# Ethernet.net
KiCad netlist of a schematic drawn in Altium Designer
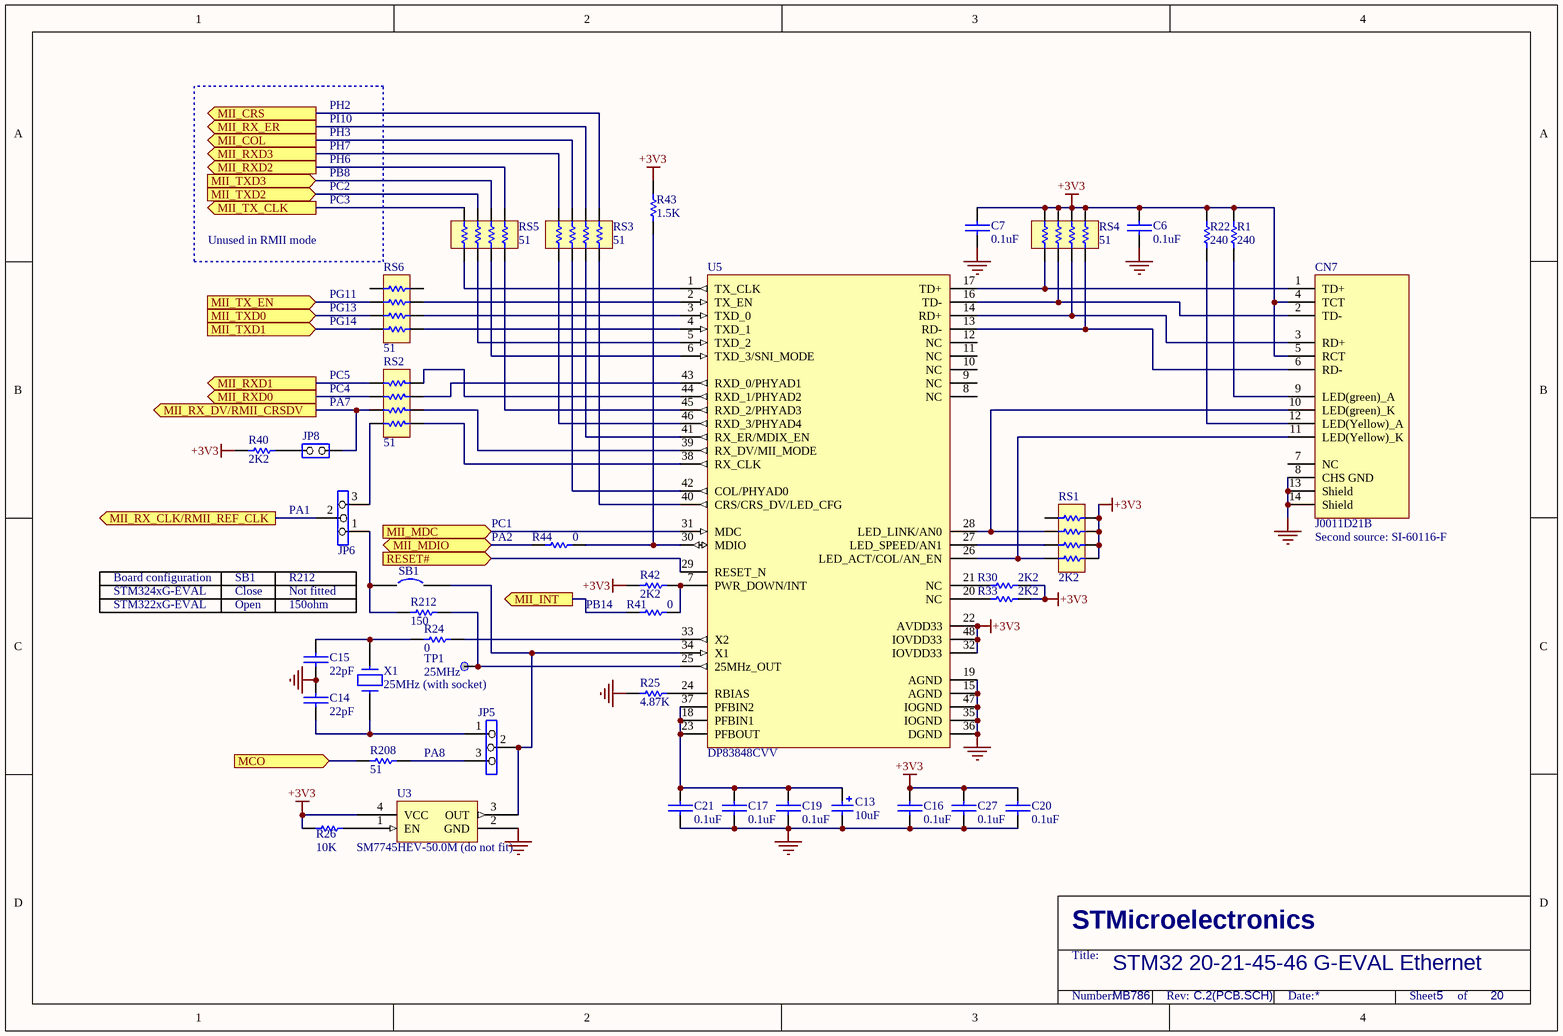
[diagram p0: Ethernet.SchDoc]

(export (version "E")
  (design (tool "Eeschema 10.0.6"))
  (components
    (comp (ref "C6")
      (value "0.1uF")
      (footprint "0402C")
      (description "Capacitor")
      (libsource (lib "*") (part "CAP"))
    )
    (comp (ref "C7")
      (value "0.1uF")
      (footprint "0402C")
      (description "Capacitor")
      (libsource (lib "*") (part "CAP"))
    )
    (comp (ref "C13")
      (value "10uF")
      (footprint "TAN-A")
      (description "Polarized Capacitor (Radial)")
      (fields (field (name "PUBLISHER") "Altium Limited"))
      (libsource (lib "Miscellaneous Devices") (part "Cap Pol1"))
    )
    (comp (ref "C14")
      (value "22pF")
      (footprint "0603C")
      (description "Capacitor")
      (libsource (lib "*") (part "CAP"))
    )
    (comp (ref "C15")
      (value "22pF")
      (footprint "0603C")
      (description "Capacitor")
      (libsource (lib "*") (part "CAP"))
    )
    (comp (ref "C16")
      (value "0.1uF")
      (footprint "0402C")
      (description "Capacitor")
      (libsource (lib "*") (part "CAP"))
    )
    (comp (ref "C17")
      (value "0.1uF")
      (footprint "0402C")
      (description "Capacitor")
      (libsource (lib "*") (part "CAP"))
    )
    (comp (ref "C19")
      (value "0.1uF")
      (footprint "0402C")
      (description "Capacitor")
      (libsource (lib "*") (part "CAP"))
    )
    (comp (ref "C20")
      (value "0.1uF")
      (footprint "0402C")
      (description "Capacitor")
      (libsource (lib "*") (part "CAP"))
    )
    (comp (ref "C21")
      (value "0.1uF")
      (footprint "0402C")
      (description "Capacitor")
      (libsource (lib "*") (part "CAP"))
    )
    (comp (ref "C27")
      (value "0.1uF")
      (footprint "0402C")
      (description "Capacitor")
      (libsource (lib "*") (part "CAP"))
    )
    (comp (ref "CN7")
      (value "J0011D21B")
      (footprint "J0011D21B")
      (libsource (lib "MB784") (part "J0011D21B"))
    )
    (comp (ref "JP5") (value "~") (footprint "SIP3") (libsource (lib "STR910_SCHLIB") (part "Jumper3")))
    (comp (ref "JP6") (value "~") (footprint "SIP3") (libsource (lib "STR910_SCHLIB") (part "Jumper3")))
    (comp (ref "JP8") (value "~") (footprint "SIP2") (libsource (lib "*") (part "JP2")))
    (comp (ref "R1")
      (value "240")
      (footprint "0603R")
      (description "Resistor")
      (fields (field (name "PUBLISHER") "Altium Limited"))
      (libsource (lib "Miscellaneous Devices") (part "Res1"))
    )
    (comp (ref "R22")
      (value "240")
      (footprint "0603R")
      (description "Resistor")
      (fields (field (name "PUBLISHER") "Altium Limited"))
      (libsource (lib "Miscellaneous Devices") (part "Res1"))
    )
    (comp (ref "R24")
      (value "0")
      (footprint "0603R")
      (description "Resistor")
      (fields (field (name "PUBLISHER") "Altium Limited"))
      (libsource (lib "Miscellaneous Devices") (part "Res1"))
    )
    (comp (ref "R25")
      (value "4.87K")
      (footprint "0603R")
      (description "Resistor")
      (fields (field (name "PUBLISHER") "Altium Limited"))
      (libsource (lib "Miscellaneous Devices") (part "Res1"))
    )
    (comp (ref "R26")
      (value "10K")
      (footprint "0402R")
      (description "Resistor")
      (fields (field (name "PUBLISHER") "Altium Limited"))
      (libsource (lib "Miscellaneous Devices") (part "Res1"))
    )
    (comp (ref "R30")
      (value "2K2")
      (footprint "0603R")
      (description "Resistor")
      (fields (field (name "PUBLISHER") "Altium Limited"))
      (libsource (lib "Miscellaneous Devices") (part "Res1"))
    )
    (comp (ref "R33")
      (value "2K2")
      (footprint "0603R")
      (description "Resistor")
      (fields (field (name "PUBLISHER") "Altium Limited"))
      (libsource (lib "Miscellaneous Devices") (part "Res1"))
    )
    (comp (ref "R40")
      (value "2K2")
      (footprint "0603R")
      (description "Resistor")
      (fields (field (name "PUBLISHER") "Altium Limited"))
      (libsource (lib "Miscellaneous Devices") (part "Res1"))
    )
    (comp (ref "R41")
      (value "0")
      (footprint "0603R")
      (description "Resistor")
      (fields (field (name "PUBLISHER") "Altium Limited"))
      (libsource (lib "Miscellaneous Devices") (part "Res1"))
    )
    (comp (ref "R42")
      (value "2K2")
      (footprint "0603R")
      (description "Resistor")
      (fields (field (name "PUBLISHER") "Altium Limited"))
      (libsource (lib "Miscellaneous Devices") (part "Res1"))
    )
    (comp (ref "R43")
      (value "1.5K")
      (footprint "0603R")
      (description "Resistor")
      (fields (field (name "PUBLISHER") "Altium Limited"))
      (libsource (lib "Miscellaneous Devices") (part "Res1"))
    )
    (comp (ref "R44")
      (value "0")
      (footprint "0603R")
      (description "Resistor")
      (fields (field (name "PUBLISHER") "Altium Limited"))
      (libsource (lib "Miscellaneous Devices") (part "Res1"))
    )
    (comp (ref "R208")
      (value "51")
      (footprint "0603R")
      (description "Resistor")
      (fields (field (name "PUBLISHER") "Altium Limited"))
      (libsource (lib "Miscellaneous Devices") (part "Res1"))
    )
    (comp (ref "R212")
      (value "150")
      (footprint "0603R")
      (description "Resistor")
      (fields (field (name "PUBLISHER") "Altium Limited"))
      (libsource (lib "Miscellaneous Devices") (part "Res1"))
    )
    (comp (ref "RS1") (value "2K2") (footprint "RES4B") (libsource (lib "MB784") (part "Resister Array")))
    (comp (ref "RS2") (value "51") (footprint "RES4B") (libsource (lib "*") (part "Resister Array")))
    (comp (ref "RS3") (value "51") (footprint "RES4B") (libsource (lib "") (part "Resister Array_2")))
    (comp (ref "RS4") (value "51") (footprint "RES4B") (libsource (lib "") (part "Resister Array_1")))
    (comp (ref "RS5") (value "51") (footprint "RES4B") (libsource (lib "") (part "Resister Array_2")))
    (comp (ref "RS6") (value "51") (footprint "RES4B") (libsource (lib "MB784") (part "Resister Array")))
    (comp (ref "SB1")
      (value "~")
      (footprint "JP2_SMD")
      (description "Circuit Breaker")
      (fields (field (name "PUBLISHER") "Altium Limited"))
      (libsource (lib "Miscellaneous Devices") (part "Circuit Breaker"))
    )
    (comp (ref "TP1") (value "25MHz") (footprint "TP") (libsource (lib "*") (part "TP")))
    (comp (ref "U3")
      (value "SM7745HEV-50.0M (do not fit)")
      (footprint "XTAL_5X7")
      (libsource (lib "MB784") (part "SM7745HEV-50.0M"))
    )
    (comp (ref "U5") (value "DP83848CVV") (footprint "LQFP48") (libsource (lib "MB784") (part "DP83848CVV")))
    (comp (ref "X1")
      (value "25MHz (with socket)")
      (footprint "XTAL_socket")
      (description "Crystal")
      (libsource (lib "*") (part "CRYSTAL"))
    )
  )
  (nets
    (net (code "1") (name "+3V3") (class "Default")
      (node (ref "C16") (pin "1") (pinfunction "1_1") (pintype "passive"))
      (node (ref "C20") (pin "2") (pinfunction "2_2") (pintype "passive"))
      (node (ref "C27") (pin "2") (pinfunction "2_2") (pintype "passive"))
      (node (ref "C6") (pin "2") (pinfunction "2_2") (pintype "passive"))
      (node (ref "C7") (pin "2") (pinfunction "2_2") (pintype "passive"))
      (node (ref "CN7") (pin "4") (pinfunction "TCT_4") (pintype "passive"))
      (node (ref "CN7") (pin "5") (pinfunction "RCT_5") (pintype "passive"))
      (node (ref "R1") (pin "2") (pinfunction "2_2") (pintype "passive"))
      (node (ref "R22") (pin "2") (pinfunction "2_2") (pintype "passive"))
      (node (ref "R26") (pin "1") (pinfunction "1_1") (pintype "passive"))
      (node (ref "R30") (pin "2") (pinfunction "2_2") (pintype "passive"))
      (node (ref "R33") (pin "2") (pinfunction "2_2") (pintype "passive"))
      (node (ref "R40") (pin "2") (pinfunction "2_2") (pintype "passive"))
      (node (ref "R42") (pin "1") (pinfunction "1_1") (pintype "passive"))
      (node (ref "R43") (pin "2") (pinfunction "2_2") (pintype "passive"))
      (node (ref "RS1") (pin "1") (pinfunction "1_1") (pintype "passive"))
      (node (ref "RS1") (pin "3") (pinfunction "3_3") (pintype "passive"))
      (node (ref "RS1") (pin "5") (pinfunction "5_5") (pintype "passive"))
      (node (ref "RS1") (pin "7") (pinfunction "7_7") (pintype "passive"))
      (node (ref "RS4") (pin "1") (pinfunction "1_1") (pintype "passive"))
      (node (ref "RS4") (pin "3") (pinfunction "3_3") (pintype "passive"))
      (node (ref "RS4") (pin "5") (pinfunction "5_5") (pintype "passive"))
      (node (ref "RS4") (pin "7") (pinfunction "7_7") (pintype "passive"))
      (node (ref "U3") (pin "4") (pinfunction "VCC_4") (pintype "passive"))
      (node (ref "U5") (pin "22") (pinfunction "AVDD33_22") (pintype "passive"))
      (node (ref "U5") (pin "32") (pinfunction "IOVDD33_32") (pintype "passive"))
      (node (ref "U5") (pin "48") (pinfunction "IOVDD33_48") (pintype "passive"))
    )
    (net (code "2") (name "/MCO") (class "Default")
      (node (ref "R208") (pin "2") (pinfunction "2_2") (pintype "passive"))
    )
    (net (code "3") (name "/MII_COL") (class "Default")
      (node (ref "RS3") (pin "4") (pinfunction "4_4") (pintype "passive"))
    )
    (net (code "4") (name "/MII_CRS") (class "Default")
      (node (ref "RS3") (pin "8") (pinfunction "8_8") (pintype "passive"))
    )
    (net (code "5") (name "/MII_INT") (class "Default")
      (node (ref "R41") (pin "1") (pinfunction "1_1") (pintype "passive"))
    )
    (net (code "6") (name "/MII_MDC") (class "Default")
      (node (ref "U5") (pin "31") (pinfunction "MDC_31") (pintype "input"))
    )
    (net (code "7") (name "/MII_MDIO") (class "Default")
      (node (ref "R44") (pin "1") (pinfunction "1_1") (pintype "passive"))
    )
    (net (code "8") (name "/MII_RXD0") (class "Default")
      (node (ref "RS2") (pin "4") (pinfunction "4_4") (pintype "passive"))
    )
    (net (code "9") (name "/MII_RXD1") (class "Default")
      (node (ref "RS2") (pin "2") (pinfunction "2_2") (pintype "passive"))
    )
    (net (code "10") (name "/MII_RXD2") (class "Default")
      (node (ref "RS5") (pin "8") (pinfunction "8_8") (pintype "passive"))
    )
    (net (code "11") (name "/MII_RXD3") (class "Default")
      (node (ref "RS3") (pin "2") (pinfunction "2_2") (pintype "passive"))
    )
    (net (code "12") (name "/MII_RX_CLK{slash}RMII_REF_CLK") (class "Default")
      (node (ref "JP6") (pin "2") (pintype "passive"))
    )
    (net (code "13") (name "/MII_RX_DV{slash}RMII_CRSDV") (class "Default")
      (node (ref "JP8") (pin "1") (pinfunction "COMMON_1") (pintype "passive"))
      (node (ref "RS2") (pin "6") (pinfunction "6_6") (pintype "passive"))
    )
    (net (code "14") (name "/MII_RX_ER") (class "Default")
      (node (ref "RS3") (pin "6") (pinfunction "6_6") (pintype "passive"))
    )
    (net (code "15") (name "/MII_TXD0") (class "Default")
      (node (ref "RS6") (pin "4") (pinfunction "4_4") (pintype "passive"))
    )
    (net (code "16") (name "/MII_TXD1") (class "Default")
      (node (ref "RS6") (pin "2") (pinfunction "2_2") (pintype "passive"))
    )
    (net (code "17") (name "/MII_TXD2") (class "Default")
      (node (ref "RS5") (pin "4") (pinfunction "4_4") (pintype "passive"))
    )
    (net (code "18") (name "/MII_TXD3") (class "Default")
      (node (ref "RS5") (pin "6") (pinfunction "6_6") (pintype "passive"))
    )
    (net (code "19") (name "/MII_TX_CLK") (class "Default")
      (node (ref "RS5") (pin "2") (pinfunction "2_2") (pintype "passive"))
    )
    (net (code "20") (name "/MII_TX_EN") (class "Default")
      (node (ref "RS6") (pin "6") (pinfunction "6_6") (pintype "passive"))
    )
    (net (code "21") (name "/RESET#") (class "Default")
      (node (ref "U5") (pin "29") (pinfunction "RESET_N_29") (pintype "passive"))
    )
    (net (code "22") (name "GND") (class "Default")
      (node (ref "C13") (pin "2") (pinfunction "2_2") (pintype "passive"))
      (node (ref "C14") (pin "2") (pinfunction "2_2") (pintype "passive"))
      (node (ref "C15") (pin "1") (pinfunction "1_1") (pintype "passive"))
      (node (ref "C16") (pin "2") (pinfunction "2_2") (pintype "passive"))
      (node (ref "C17") (pin "1") (pinfunction "1_1") (pintype "passive"))
      (node (ref "C19") (pin "1") (pinfunction "1_1") (pintype "passive"))
      (node (ref "C20") (pin "1") (pinfunction "1_1") (pintype "passive"))
      (node (ref "C21") (pin "2") (pinfunction "2_2") (pintype "passive"))
      (node (ref "C27") (pin "1") (pinfunction "1_1") (pintype "passive"))
      (node (ref "C6") (pin "1") (pinfunction "1_1") (pintype "passive"))
      (node (ref "C7") (pin "1") (pinfunction "1_1") (pintype "passive"))
      (node (ref "CN7") (pin "13") (pinfunction "Shield_13") (pintype "passive"))
      (node (ref "CN7") (pin "14") (pinfunction "Shield_14") (pintype "passive"))
      (node (ref "CN7") (pin "8") (pinfunction "CHS_GND_8") (pintype "passive"))
      (node (ref "R25") (pin "1") (pinfunction "1_1") (pintype "passive"))
      (node (ref "U3") (pin "2") (pinfunction "GND_2") (pintype "passive"))
      (node (ref "U5") (pin "15") (pinfunction "AGND_15") (pintype "passive"))
      (node (ref "U5") (pin "19") (pinfunction "AGND_19") (pintype "passive"))
      (node (ref "U5") (pin "35") (pinfunction "IOGND_35") (pintype "passive"))
      (node (ref "U5") (pin "36") (pinfunction "DGND_36") (pintype "passive"))
      (node (ref "U5") (pin "47") (pinfunction "IOGND_47") (pintype "passive"))
    )
    (net (code "23") (name "Net-(C14-Pad1)") (class "Default")
      (node (ref "C14") (pin "1") (pinfunction "1_1") (pintype "passive"))
      (node (ref "JP5") (pin "1") (pintype "passive"))
      (node (ref "X1") (pin "1") (pinfunction "1_1") (pintype "passive"))
    )
    (net (code "24") (name "Net-(C15-Pad2)") (class "Default")
      (node (ref "C15") (pin "2") (pinfunction "2_2") (pintype "passive"))
      (node (ref "R24") (pin "2") (pinfunction "2_2") (pintype "passive"))
      (node (ref "X1") (pin "2") (pinfunction "2_2") (pintype "passive"))
    )
    (net (code "25") (name "Net-(CN7-LED(Yellow)_A)") (class "Default")
      (node (ref "CN7") (pin "12") (pinfunction "LED(Yellow)_A_12") (pintype "passive"))
      (node (ref "R22") (pin "1") (pinfunction "1_1") (pintype "passive"))
    )
    (net (code "26") (name "Net-(CN7-LED(Yellow)_K)") (class "Default")
      (node (ref "CN7") (pin "11") (pinfunction "LED(Yellow)_K_11") (pintype "passive"))
      (node (ref "RS1") (pin "2") (pinfunction "2_2") (pintype "passive"))
      (node (ref "U5") (pin "26") (pinfunction "LED_ACT/COL/AN_EN_26") (pintype "passive"))
    )
    (net (code "27") (name "Net-(CN7-LED(green)_A)") (class "Default")
      (node (ref "CN7") (pin "9") (pinfunction "LED(green)_A_9") (pintype "passive"))
      (node (ref "R1") (pin "1") (pinfunction "1_1") (pintype "passive"))
    )
    (net (code "28") (name "Net-(CN7-LED(green)_K)") (class "Default")
      (node (ref "CN7") (pin "10") (pinfunction "LED(green)_K_10") (pintype "passive"))
      (node (ref "RS1") (pin "6") (pinfunction "6_6") (pintype "passive"))
      (node (ref "U5") (pin "28") (pinfunction "LED_LINK/AN0_28") (pintype "passive"))
    )
    (net (code "29") (name "Net-(CN7-RD+)") (class "Default")
      (node (ref "CN7") (pin "3") (pinfunction "RD+_3") (pintype "passive"))
      (node (ref "RS4") (pin "4") (pinfunction "4_4") (pintype "passive"))
      (node (ref "U5") (pin "14") (pinfunction "RD+_14") (pintype "passive"))
    )
    (net (code "30") (name "Net-(CN7-RD-)") (class "Default")
      (node (ref "CN7") (pin "6") (pinfunction "RD-_6") (pintype "passive"))
      (node (ref "RS4") (pin "2") (pinfunction "2_2") (pintype "passive"))
      (node (ref "U5") (pin "13") (pinfunction "RD-_13") (pintype "passive"))
    )
    (net (code "31") (name "Net-(CN7-TD+)") (class "Default")
      (node (ref "CN7") (pin "1") (pinfunction "TD+_1") (pintype "passive"))
      (node (ref "RS4") (pin "8") (pinfunction "8_8") (pintype "passive"))
      (node (ref "U5") (pin "17") (pinfunction "TD+_17") (pintype "passive"))
    )
    (net (code "32") (name "Net-(CN7-TD-)") (class "Default")
      (node (ref "CN7") (pin "2") (pinfunction "TD-_2") (pintype "passive"))
      (node (ref "RS4") (pin "6") (pinfunction "6_6") (pintype "passive"))
      (node (ref "U5") (pin "16") (pinfunction "TD-_16") (pintype "passive"))
    )
    (net (code "33") (name "Net-(JP5-Pad3)") (class "Default")
      (node (ref "JP5") (pin "3") (pintype "passive"))
      (node (ref "R208") (pin "1") (pinfunction "1_1") (pintype "passive"))
    )
    (net (code "34") (name "Net-(JP6-Pad1)") (class "Default")
      (node (ref "JP6") (pin "1") (pintype "passive"))
      (node (ref "R212") (pin "2") (pinfunction "2_2") (pintype "passive"))
      (node (ref "SB1") (pin "1") (pinfunction "1_1") (pintype "passive"))
    )
    (net (code "35") (name "Net-(JP6-Pad3)") (class "Default")
      (node (ref "JP6") (pin "3") (pintype "passive"))
      (node (ref "RS2") (pin "8") (pinfunction "8_8") (pintype "passive"))
    )
    (net (code "36") (name "Net-(JP8-NO)") (class "Default")
      (node (ref "JP8") (pin "2") (pinfunction "NO_2") (pintype "passive"))
      (node (ref "R40") (pin "1") (pinfunction "1_1") (pintype "passive"))
    )
    (net (code "37") (name "Net-(R30-Pad1)") (class "Default")
      (node (ref "R30") (pin "1") (pinfunction "1_1") (pintype "passive"))
      (node (ref "U5") (pin "21") (pinfunction "NC_21") (pintype "passive"))
    )
    (net (code "38") (name "Net-(R33-Pad1)") (class "Default")
      (node (ref "R33") (pin "1") (pinfunction "1_1") (pintype "passive"))
      (node (ref "U5") (pin "20") (pinfunction "NC_20") (pintype "passive"))
    )
    (net (code "39") (name "Net-(U3-EN)") (class "Default")
      (node (ref "R26") (pin "2") (pinfunction "2_2") (pintype "passive"))
      (node (ref "U3") (pin "1") (pinfunction "EN_1") (pintype "input"))
    )
    (net (code "40") (name "Net-(U3-OUT)") (class "Default")
      (node (ref "JP5") (pin "2") (pintype "passive"))
      (node (ref "SB1") (pin "2") (pinfunction "2_2") (pintype "passive"))
      (node (ref "U3") (pin "3") (pinfunction "OUT_3") (pintype "output"))
      (node (ref "U5") (pin "34") (pinfunction "X1_34") (pintype "input"))
    )
    (net (code "41") (name "Net-(U5-25MHz_OUT)") (class "Default")
      (node (ref "R212") (pin "1") (pinfunction "1_1") (pintype "passive"))
      (node (ref "TP1") (pin "1") (pinfunction "1_1") (pintype "passive"))
      (node (ref "U5") (pin "25") (pinfunction "25MHz_OUT_25") (pintype "output"))
    )
    (net (code "42") (name "Net-(U5-COL{slash}PHYAD0)") (class "Default")
      (node (ref "RS3") (pin "3") (pinfunction "3_3") (pintype "passive"))
      (node (ref "U5") (pin "42") (pinfunction "COL/PHYAD0_42") (pintype "output"))
    )
    (net (code "43") (name "Net-(U5-CRS{slash}CRS_DV{slash}LED_CFG)") (class "Default")
      (node (ref "RS3") (pin "7") (pinfunction "7_7") (pintype "passive"))
      (node (ref "U5") (pin "40") (pinfunction "CRS/CRS_DV/LED_CFG_40") (pintype "output"))
    )
    (net (code "44") (name "Net-(U5-LED_SPEED{slash}AN1)") (class "Default")
      (node (ref "RS1") (pin "4") (pinfunction "4_4") (pintype "passive"))
      (node (ref "U5") (pin "27") (pinfunction "LED_SPEED/AN1_27") (pintype "passive"))
    )
    (net (code "45") (name "Net-(U5-MDIO)") (class "Default")
      (node (ref "R43") (pin "1") (pinfunction "1_1") (pintype "passive"))
      (node (ref "R44") (pin "2") (pinfunction "2_2") (pintype "passive"))
      (node (ref "U5") (pin "30") (pinfunction "MDIO_30") (pintype "bidirectional"))
    )
    (net (code "46") (name "Net-(U5-PFBIN1)") (class "Default")
      (node (ref "C13") (pin "1") (pinfunction "1_1") (pintype "passive"))
      (node (ref "C17") (pin "2") (pinfunction "2_2") (pintype "passive"))
      (node (ref "C19") (pin "2") (pinfunction "2_2") (pintype "passive"))
      (node (ref "C21") (pin "1") (pinfunction "1_1") (pintype "passive"))
      (node (ref "U5") (pin "18") (pinfunction "PFBIN1_18") (pintype "passive"))
      (node (ref "U5") (pin "23") (pinfunction "PFBOUT_23") (pintype "passive"))
      (node (ref "U5") (pin "37") (pinfunction "PFBIN2_37") (pintype "passive"))
    )
    (net (code "47") (name "Net-(U5-PWR_DOWN{slash}INT)") (class "Default")
      (node (ref "R41") (pin "2") (pinfunction "2_2") (pintype "passive"))
      (node (ref "R42") (pin "2") (pinfunction "2_2") (pintype "passive"))
      (node (ref "U5") (pin "7") (pinfunction "PWR_DOWN/INT_7") (pintype "passive"))
    )
    (net (code "48") (name "Net-(U5-RBIAS)") (class "Default")
      (node (ref "R25") (pin "2") (pinfunction "2_2") (pintype "passive"))
      (node (ref "U5") (pin "24") (pinfunction "RBIAS_24") (pintype "passive"))
    )
    (net (code "49") (name "Net-(U5-RXD_0{slash}PHYAD1)") (class "Default")
      (node (ref "RS2") (pin "3") (pinfunction "3_3") (pintype "passive"))
      (node (ref "U5") (pin "43") (pinfunction "RXD_0/PHYAD1_43") (pintype "output"))
    )
    (net (code "50") (name "Net-(U5-RXD_1{slash}PHYAD2)") (class "Default")
      (node (ref "RS2") (pin "1") (pinfunction "1_1") (pintype "passive"))
      (node (ref "U5") (pin "44") (pinfunction "RXD_1/PHYAD2_44") (pintype "output"))
    )
    (net (code "51") (name "Net-(U5-RXD_2{slash}PHYAD3)") (class "Default")
      (node (ref "RS5") (pin "7") (pinfunction "7_7") (pintype "passive"))
      (node (ref "U5") (pin "45") (pinfunction "RXD_2/PHYAD3_45") (pintype "output"))
    )
    (net (code "52") (name "Net-(U5-RXD_3{slash}PHYAD4)") (class "Default")
      (node (ref "RS3") (pin "1") (pinfunction "1_1") (pintype "passive"))
      (node (ref "U5") (pin "46") (pinfunction "RXD_3/PHYAD4_46") (pintype "output"))
    )
    (net (code "53") (name "Net-(U5-RX_CLK)") (class "Default")
      (node (ref "RS2") (pin "7") (pinfunction "7_7") (pintype "passive"))
      (node (ref "U5") (pin "38") (pinfunction "RX_CLK_38") (pintype "output"))
    )
    (net (code "54") (name "Net-(U5-RX_DV{slash}MII_MODE)") (class "Default")
      (node (ref "RS2") (pin "5") (pinfunction "5_5") (pintype "passive"))
      (node (ref "U5") (pin "39") (pinfunction "RX_DV/MII_MODE_39") (pintype "output"))
    )
    (net (code "55") (name "Net-(U5-RX_ER{slash}MDIX_EN)") (class "Default")
      (node (ref "RS3") (pin "5") (pinfunction "5_5") (pintype "passive"))
      (node (ref "U5") (pin "41") (pinfunction "RX_ER/MDIX_EN_41") (pintype "output"))
    )
    (net (code "56") (name "Net-(U5-TXD_0)") (class "Default")
      (node (ref "RS6") (pin "3") (pinfunction "3_3") (pintype "passive"))
      (node (ref "U5") (pin "3") (pinfunction "TXD_0_3") (pintype "input"))
    )
    (net (code "57") (name "Net-(U5-TXD_1)") (class "Default")
      (node (ref "RS6") (pin "1") (pinfunction "1_1") (pintype "passive"))
      (node (ref "U5") (pin "4") (pinfunction "TXD_1_4") (pintype "input"))
    )
    (net (code "58") (name "Net-(U5-TXD_2)") (class "Default")
      (node (ref "RS5") (pin "3") (pinfunction "3_3") (pintype "passive"))
      (node (ref "U5") (pin "5") (pinfunction "TXD_2_5") (pintype "input"))
    )
    (net (code "59") (name "Net-(U5-TXD_3{slash}SNI_MODE)") (class "Default")
      (node (ref "RS5") (pin "5") (pinfunction "5_5") (pintype "passive"))
      (node (ref "U5") (pin "6") (pinfunction "TXD_3/SNI_MODE_6") (pintype "input"))
    )
    (net (code "60") (name "Net-(U5-TX_CLK)") (class "Default")
      (node (ref "RS5") (pin "1") (pinfunction "1_1") (pintype "passive"))
      (node (ref "U5") (pin "1") (pinfunction "TX_CLK_1") (pintype "output"))
    )
    (net (code "61") (name "Net-(U5-TX_EN)") (class "Default")
      (node (ref "RS6") (pin "5") (pinfunction "5_5") (pintype "passive"))
      (node (ref "U5") (pin "2") (pinfunction "TX_EN_2") (pintype "input"))
    )
    (net (code "62") (name "Net-(U5-X2)") (class "Default")
      (node (ref "R24") (pin "1") (pinfunction "1_1") (pintype "passive"))
      (node (ref "U5") (pin "33") (pinfunction "X2_33") (pintype "output"))
    )
    (net (code "63") (name "unconnected-(CN7-NC-Pad7)") (class "Default")
      (node (ref "CN7") (pin "7") (pinfunction "NC_7") (pintype "passive"))
    )
    (net (code "64") (name "unconnected-(RS1-Pad8)") (class "Default")
      (node (ref "RS1") (pin "8") (pinfunction "8_8") (pintype "passive"))
    )
    (net (code "65") (name "unconnected-(RS6-Pad7)") (class "Default")
      (node (ref "RS6") (pin "7") (pinfunction "7_7") (pintype "passive"))
    )
    (net (code "66") (name "unconnected-(RS6-Pad8)") (class "Default")
      (node (ref "RS6") (pin "8") (pinfunction "8_8") (pintype "passive"))
    )
    (net (code "67") (name "unconnected-(U5-NC-Pad8)") (class "Default")
      (node (ref "U5") (pin "8") (pinfunction "NC_8") (pintype "passive"))
    )
    (net (code "68") (name "unconnected-(U5-NC-Pad9)") (class "Default")
      (node (ref "U5") (pin "9") (pinfunction "NC_9") (pintype "passive"))
    )
    (net (code "69") (name "unconnected-(U5-NC-Pad10)") (class "Default")
      (node (ref "U5") (pin "10") (pinfunction "NC_10") (pintype "passive"))
    )
    (net (code "70") (name "unconnected-(U5-NC-Pad11)") (class "Default")
      (node (ref "U5") (pin "11") (pinfunction "NC_11") (pintype "passive"))
    )
    (net (code "71") (name "unconnected-(U5-NC-Pad12)") (class "Default")
      (node (ref "U5") (pin "12") (pinfunction "NC_12") (pintype "passive"))
    )
  )
)
